# gator_UV.net
KiCad netlist of a schematic drawn in EAGLE
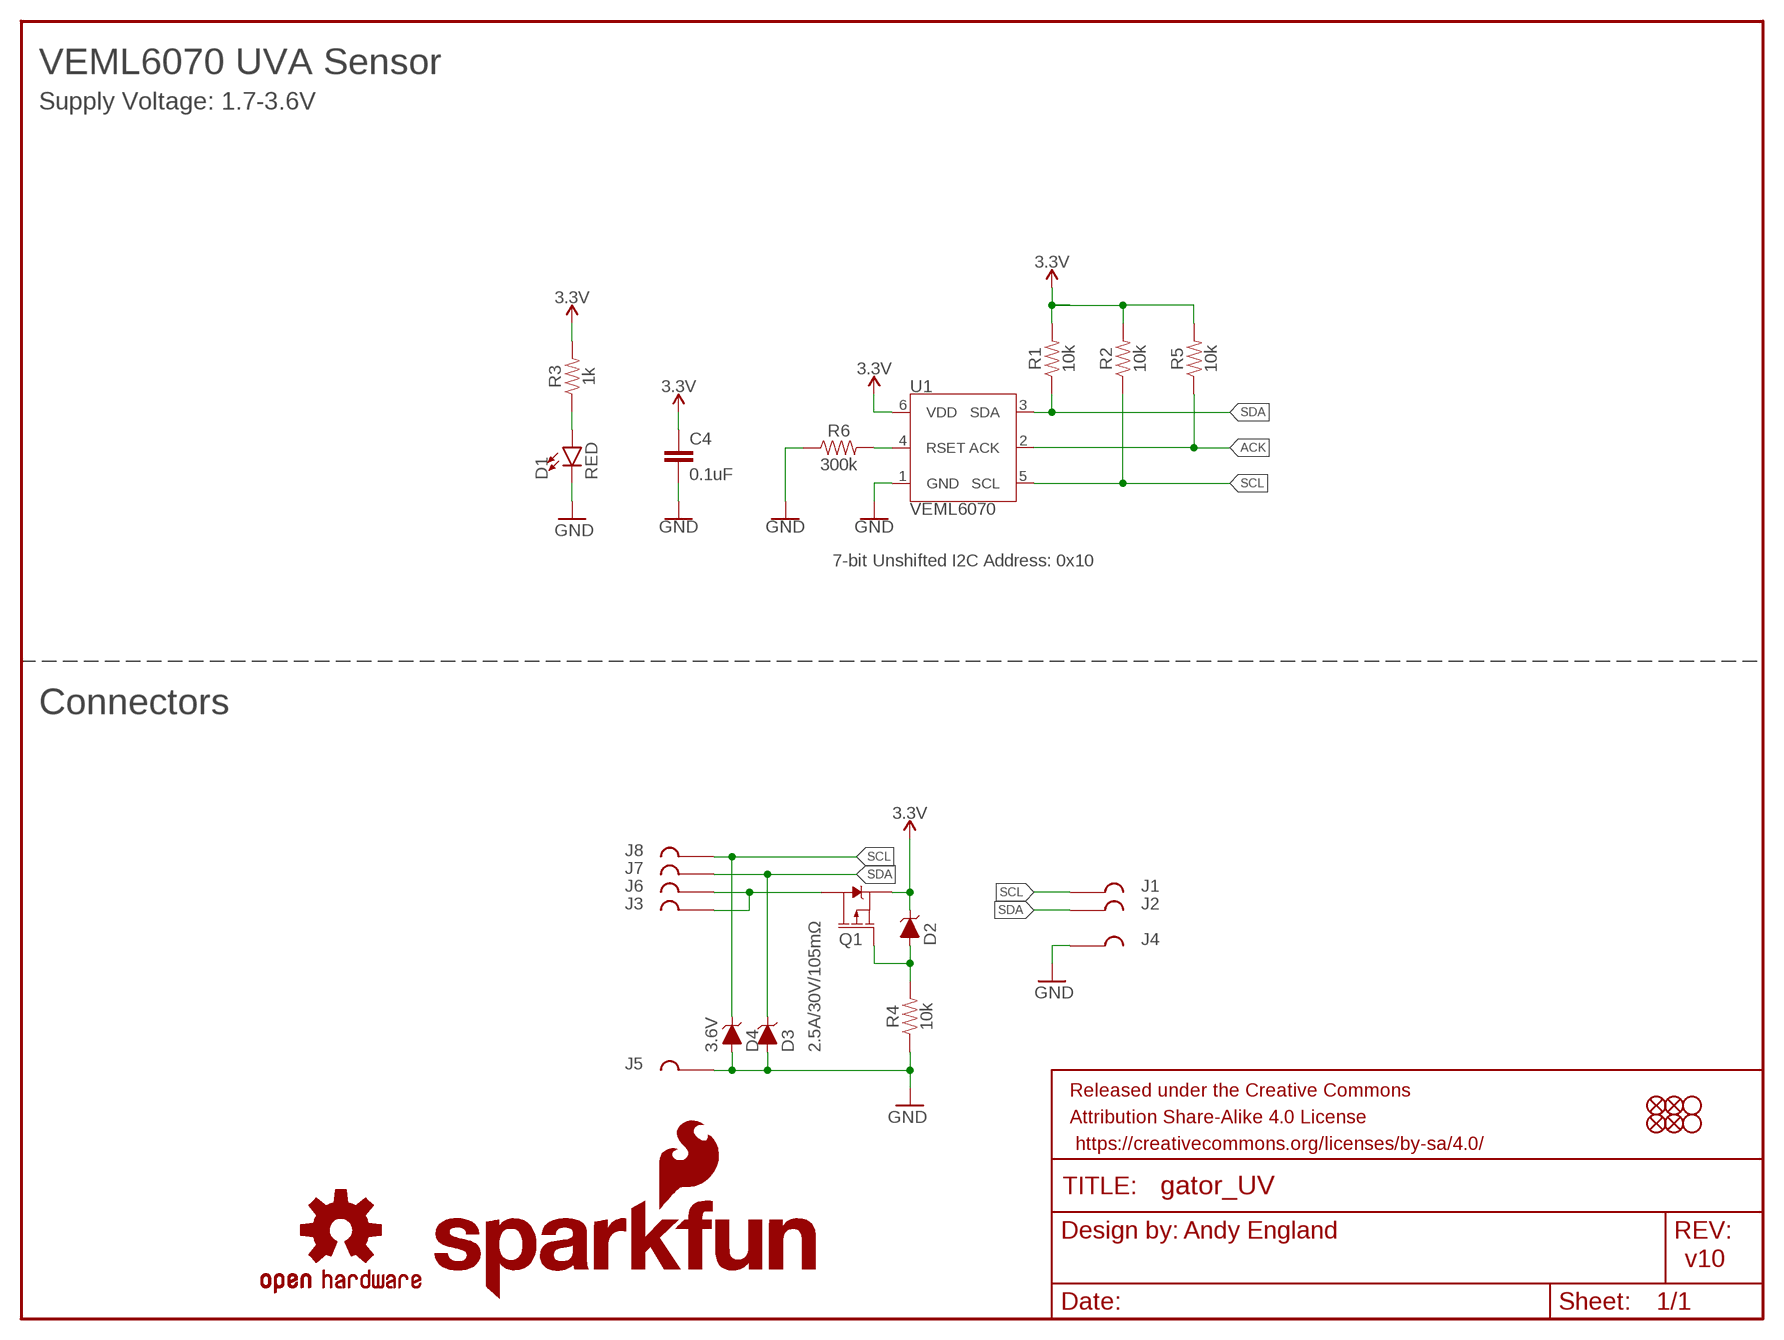
[diagram p0: schematic, sheet 1]

(export (version "E")
  (design (tool "Eeschema 10.0.6"))
  (components
    (comp (ref "C4")
      (value "0.1uF")
      (footprint "eagle-import:0603")
      (libsource (lib "eagle-import") (part "0.1UF-0603-25V-(+80/-20%)"))
    )
    (comp (ref "D1")
      (value "RED")
      (footprint "eagle-import:LED-0603")
      (libsource (lib "eagle-import") (part "LED-RED0603"))
    )
    (comp (ref "D2")
      (value "3.6V")
      (footprint "eagle-import:SOD-323")
      (libsource (lib "eagle-import") (part "DIODE-ZENER-BZT52C3V6S"))
    )
    (comp (ref "D3")
      (value "3.6V")
      (footprint "eagle-import:SOD-323")
      (libsource (lib "eagle-import") (part "DIODE-ZENER-BZT52C3V6S"))
    )
    (comp (ref "D4")
      (value "3.6V")
      (footprint "eagle-import:SOD-323")
      (libsource (lib "eagle-import") (part "DIODE-ZENER-BZT52C3V6S"))
    )
    (comp (ref "FRAME1")
      (value "FRAME-LETTER")
      (footprint "eagle-import:CREATIVE_COMMONS")
      (libsource (lib "eagle-import") (part "FRAME-LETTER"))
    )
    (comp (ref "J1")
      (value "GATORGATOR_MINI")
      (footprint "eagle-import:GATOR_MINI")
      (libsource (lib "eagle-import") (part "GATORGATOR_MINI"))
    )
    (comp (ref "J2")
      (value "GATORGATOR_MINI")
      (footprint "eagle-import:GATOR_MINI")
      (libsource (lib "eagle-import") (part "GATORGATOR_MINI"))
    )
    (comp (ref "J3")
      (value "GATORGATOR_MINI")
      (footprint "eagle-import:GATOR_MINI")
      (libsource (lib "eagle-import") (part "GATORGATOR_MINI"))
    )
    (comp (ref "J4")
      (value "GATORGATOR_MINI")
      (footprint "eagle-import:GATOR_MINI")
      (libsource (lib "eagle-import") (part "GATORGATOR_MINI"))
    )
    (comp (ref "J5")
      (value "GATORGATOR_MINI")
      (footprint "eagle-import:GATOR_MINI")
      (libsource (lib "eagle-import") (part "GATORGATOR_MINI"))
    )
    (comp (ref "J6")
      (value "GATORGATOR_MINI")
      (footprint "eagle-import:GATOR_MINI")
      (libsource (lib "eagle-import") (part "GATORGATOR_MINI"))
    )
    (comp (ref "J7")
      (value "GATORGATOR_MINI")
      (footprint "eagle-import:GATOR_MINI")
      (libsource (lib "eagle-import") (part "GATORGATOR_MINI"))
    )
    (comp (ref "J8")
      (value "GATORGATOR_MINI")
      (footprint "eagle-import:GATOR_MINI")
      (libsource (lib "eagle-import") (part "GATORGATOR_MINI"))
    )
    (comp (ref "JP2")
      (value "FIDUCIALUFIDUCIAL")
      (footprint "eagle-import:MICRO-FIDUCIAL")
      (libsource (lib "eagle-import") (part "FIDUCIALUFIDUCIAL"))
    )
    (comp (ref "JP3")
      (value "STAND-OFF")
      (footprint "eagle-import:STAND-OFF")
      (libsource (lib "eagle-import") (part "STAND-OFF"))
    )
    (comp (ref "JP4")
      (value "STAND-OFF")
      (footprint "eagle-import:STAND-OFF")
      (libsource (lib "eagle-import") (part "STAND-OFF"))
    )
    (comp (ref "JP5")
      (value "FIDUCIALUFIDUCIAL")
      (footprint "eagle-import:MICRO-FIDUCIAL")
      (libsource (lib "eagle-import") (part "FIDUCIALUFIDUCIAL"))
    )
    (comp (ref "JP6")
      (value "FIDUCIALUFIDUCIAL")
      (footprint "eagle-import:MICRO-FIDUCIAL")
      (libsource (lib "eagle-import") (part "FIDUCIALUFIDUCIAL"))
    )
    (comp (ref "JP7")
      (value "FIDUCIALUFIDUCIAL")
      (footprint "eagle-import:MICRO-FIDUCIAL")
      (libsource (lib "eagle-import") (part "FIDUCIALUFIDUCIAL"))
    )
    (comp (ref "LOGO1")
      (value "OSHW-LOGOMINI")
      (footprint "eagle-import:OSHW-LOGO-MINI")
      (libsource (lib "eagle-import") (part "OSHW-LOGOMINI"))
    )
    (comp (ref "Q1")
      (value "2.5A/30V/105mΩ")
      (footprint "eagle-import:SOT23-3")
      (libsource (lib "eagle-import") (part "MOSFET_PCH-DMG2307L"))
    )
    (comp (ref "R1")
      (value "10k")
      (footprint "eagle-import:0603")
      (libsource (lib "eagle-import") (part "10KOHM-0603-1/10W-1%"))
    )
    (comp (ref "R2")
      (value "10k")
      (footprint "eagle-import:0603")
      (libsource (lib "eagle-import") (part "10KOHM-0603-1/10W-1%"))
    )
    (comp (ref "R3")
      (value "1k")
      (footprint "eagle-import:0603")
      (libsource (lib "eagle-import") (part "1KOHM-0603-1/10W-1%"))
    )
    (comp (ref "R4")
      (value "10k")
      (footprint "eagle-import:0603")
      (libsource (lib "eagle-import") (part "10KOHM-0603-1/10W-1%"))
    )
    (comp (ref "R5")
      (value "10k")
      (footprint "eagle-import:0603")
      (libsource (lib "eagle-import") (part "10KOHM-0603-1/10W-1%"))
    )
    (comp (ref "R6")
      (value "300k")
      (footprint "eagle-import:0603")
      (libsource (lib "eagle-import") (part "300KOHM-0603-1/10W-1%"))
    )
    (comp (ref "U$1")
      (value "SFE_LOGO_NAME_FLAME.1_INCH")
      (footprint "eagle-import:SFE_LOGO_NAME_FLAME_.1")
      (libsource (lib "eagle-import") (part "SFE_LOGO_NAME_FLAME.1_INCH"))
    )
    (comp (ref "U$2")
      (value "SFE_LOGO_NAME_FLAME.1_INCH")
      (footprint "eagle-import:SFE_LOGO_NAME_FLAME_.1")
      (libsource (lib "eagle-import") (part "SFE_LOGO_NAME_FLAME.1_INCH"))
    )
    (comp (ref "U1")
      (value "VEML6070")
      (footprint "eagle-import:VEML6070")
      (libsource (lib "eagle-import") (part "VEML6070{dblquote}"))
    )
  )
  (nets
    (net (code "1") (name "3.3V") (class "Default")
      (node (ref "C4") (pin "1") (pinfunction "1_1") (pintype "passive"))
      (node (ref "D2") (pin "C") (pinfunction "C_C") (pintype "passive"))
      (node (ref "Q1") (pin "2") (pinfunction "S_2") (pintype "bidirectional"))
      (node (ref "R1") (pin "2") (pinfunction "2_2") (pintype "passive"))
      (node (ref "R2") (pin "2") (pinfunction "2_2") (pintype "passive"))
      (node (ref "R3") (pin "2") (pinfunction "2_2") (pintype "passive"))
      (node (ref "R5") (pin "2") (pinfunction "2_2") (pintype "passive"))
      (node (ref "U1") (pin "6") (pinfunction "VDD_6") (pintype "bidirectional"))
    )
    (net (code "2") (name "ACK") (class "Default")
      (node (ref "R5") (pin "1") (pinfunction "1_1") (pintype "passive"))
      (node (ref "U1") (pin "2") (pinfunction "ACK_2") (pintype "bidirectional"))
    )
    (net (code "3") (name "GND") (class "Default")
      (node (ref "C4") (pin "2") (pinfunction "2_2") (pintype "passive"))
      (node (ref "D1") (pin "C") (pinfunction "C_C") (pintype "passive"))
      (node (ref "D3") (pin "A") (pinfunction "A_A") (pintype "passive"))
      (node (ref "D4") (pin "A") (pinfunction "A_A") (pintype "passive"))
      (node (ref "J4") (pin "P$2") (pinfunction "P$1_P$2") (pintype "bidirectional"))
      (node (ref "J5") (pin "P$2") (pinfunction "P$1_P$2") (pintype "bidirectional"))
      (node (ref "R4") (pin "1") (pinfunction "1_1") (pintype "passive"))
      (node (ref "R6") (pin "1") (pinfunction "1_1") (pintype "passive"))
      (node (ref "U1") (pin "1") (pinfunction "GND_1") (pintype "bidirectional"))
    )
    (net (code "4") (name "Net-(D1-PadA)") (class "Default")
      (node (ref "D1") (pin "A") (pinfunction "A_A") (pintype "passive"))
      (node (ref "R3") (pin "1") (pinfunction "1_1") (pintype "passive"))
    )
    (net (code "5") (name "Net-(J3-P$1)") (class "Default")
      (node (ref "J3") (pin "P$2") (pinfunction "P$1_P$2") (pintype "bidirectional"))
      (node (ref "J6") (pin "P$2") (pinfunction "P$1_P$2") (pintype "bidirectional"))
      (node (ref "Q1") (pin "3") (pinfunction "D_3") (pintype "bidirectional"))
    )
    (net (code "6") (name "Net-(Q1-G)") (class "Default")
      (node (ref "D2") (pin "A") (pinfunction "A_A") (pintype "passive"))
      (node (ref "Q1") (pin "1") (pinfunction "G_1") (pintype "bidirectional"))
      (node (ref "R4") (pin "2") (pinfunction "2_2") (pintype "passive"))
    )
    (net (code "7") (name "Net-(U1-RSET)") (class "Default")
      (node (ref "R6") (pin "2") (pinfunction "2_2") (pintype "passive"))
      (node (ref "U1") (pin "4") (pinfunction "RSET_4") (pintype "bidirectional"))
    )
    (net (code "8") (name "SCL") (class "Default")
      (node (ref "D4") (pin "C") (pinfunction "C_C") (pintype "passive"))
      (node (ref "J1") (pin "P$2") (pinfunction "P$1_P$2") (pintype "bidirectional"))
      (node (ref "J8") (pin "P$2") (pinfunction "P$1_P$2") (pintype "bidirectional"))
      (node (ref "R2") (pin "1") (pinfunction "1_1") (pintype "passive"))
      (node (ref "U1") (pin "5") (pinfunction "SCL_5") (pintype "bidirectional"))
    )
    (net (code "9") (name "SDA") (class "Default")
      (node (ref "D3") (pin "C") (pinfunction "C_C") (pintype "passive"))
      (node (ref "J2") (pin "P$2") (pinfunction "P$1_P$2") (pintype "bidirectional"))
      (node (ref "J7") (pin "P$2") (pinfunction "P$1_P$2") (pintype "bidirectional"))
      (node (ref "R1") (pin "1") (pinfunction "1_1") (pintype "passive"))
      (node (ref "U1") (pin "3") (pinfunction "SDA_3") (pintype "bidirectional"))
    )
  )
)
